# NSE2022_Electro_ESPtest_ver_1.net
KiCad netlist of a schematic drawn in EAGLE
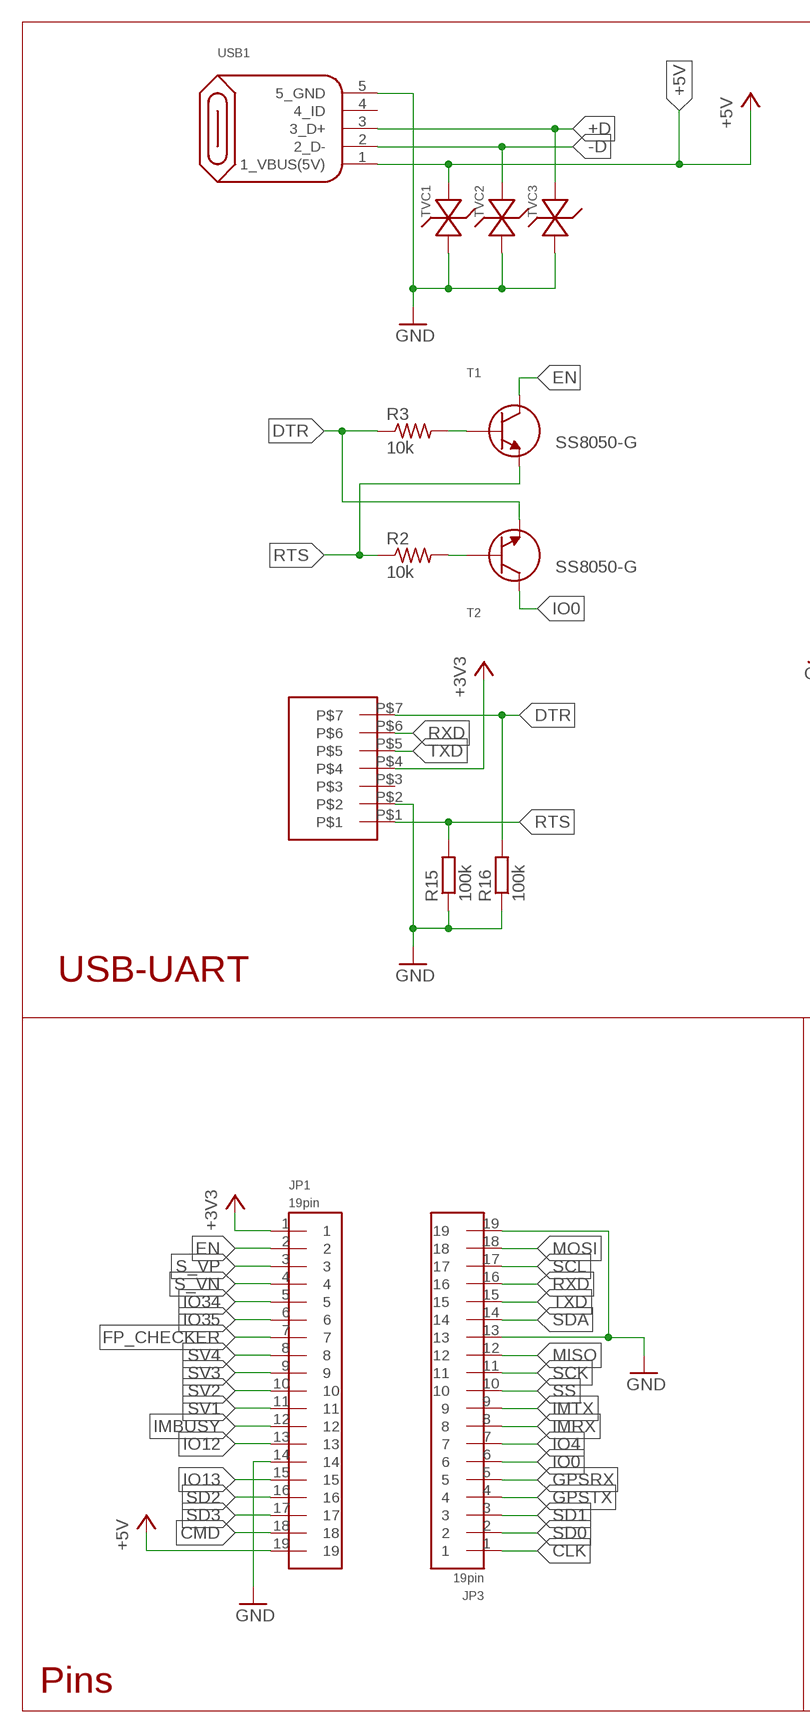
[diagram p0: schematic, sheet 1, part 1 of 2]
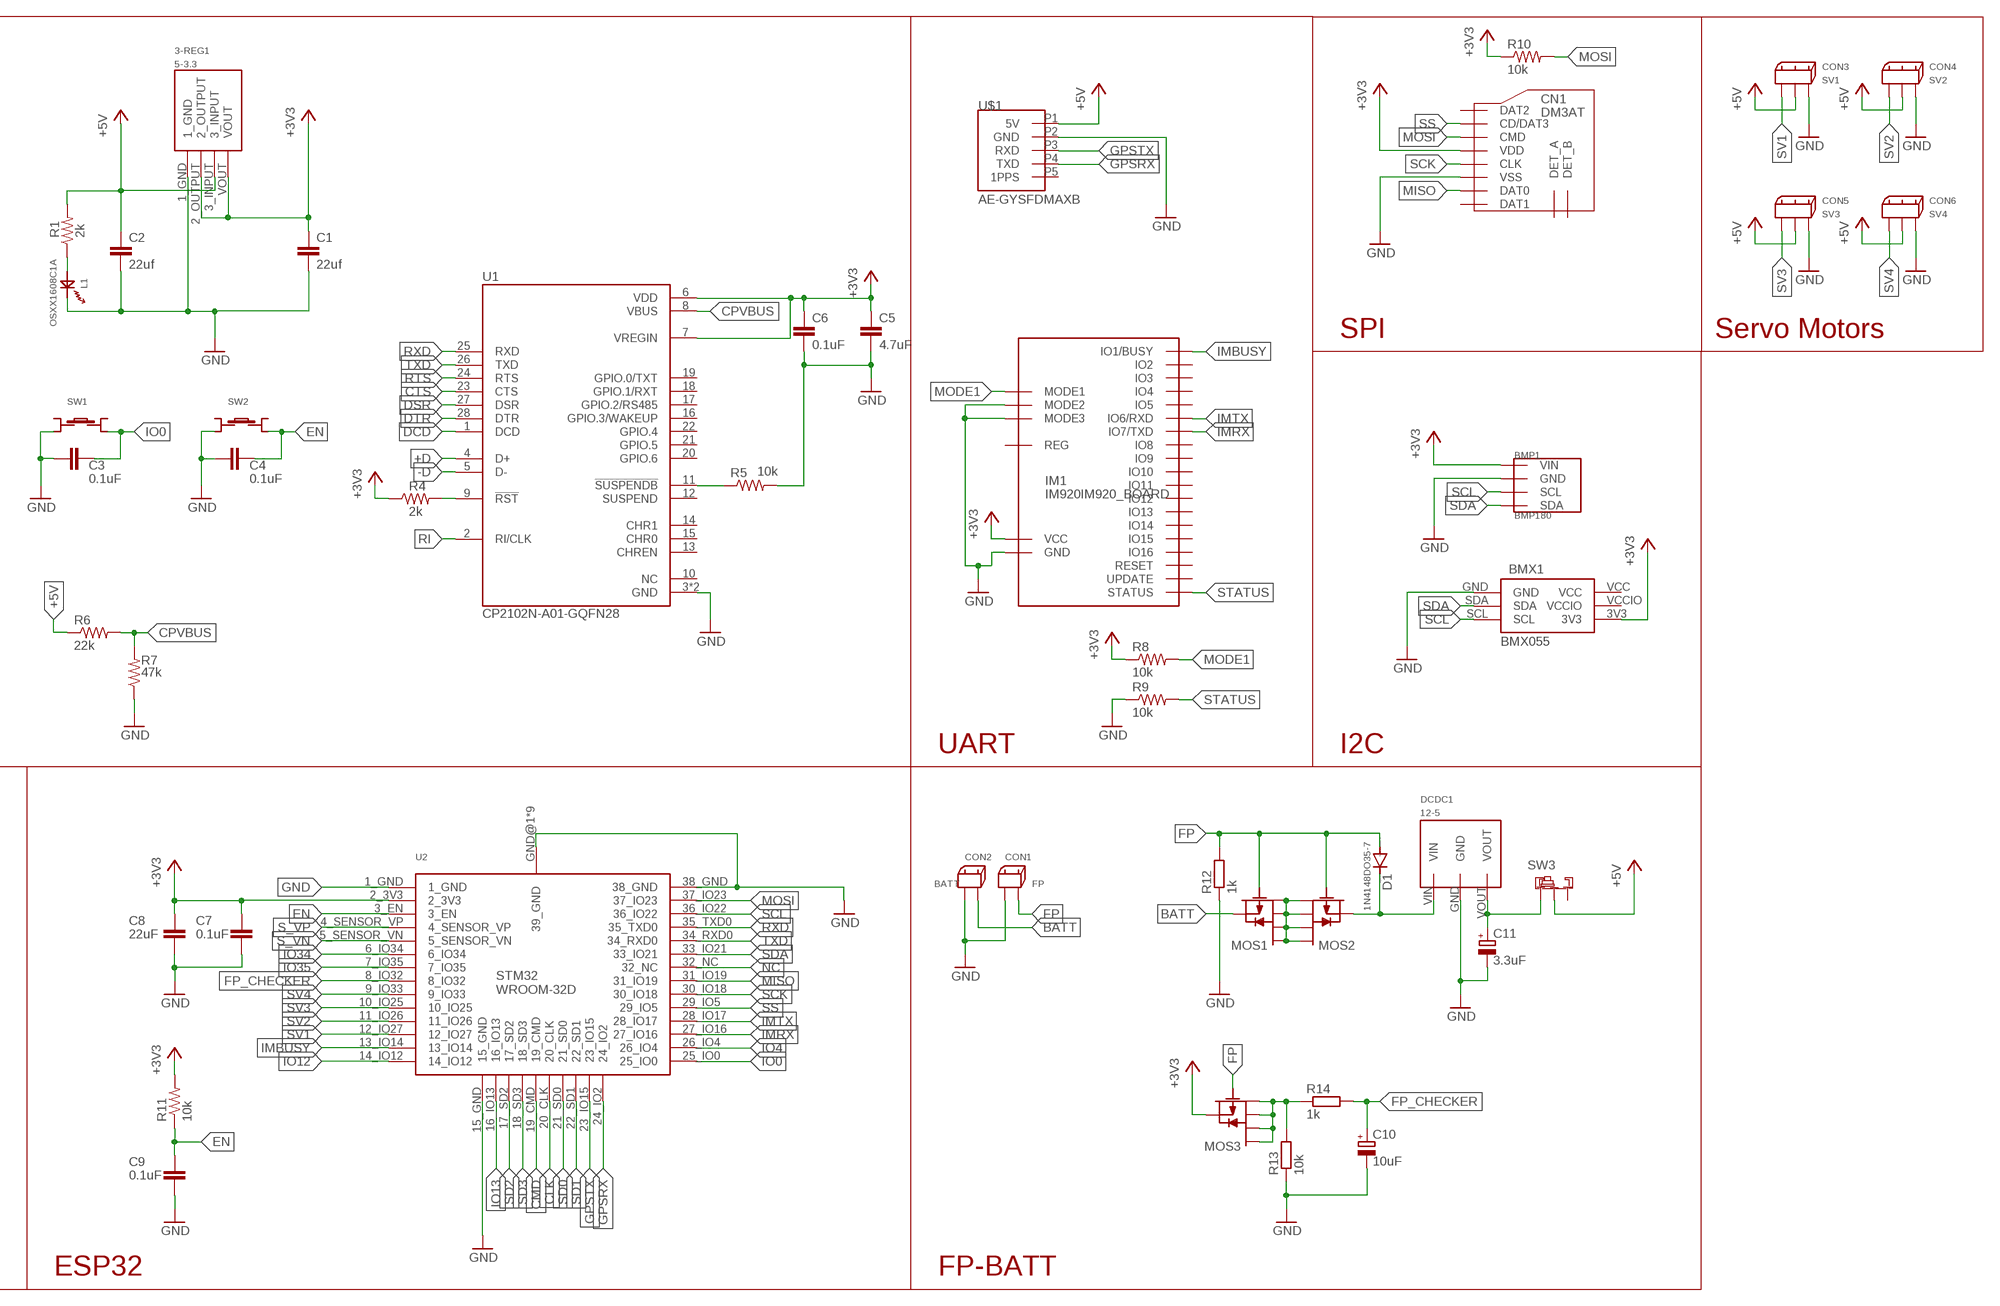
[diagram p1: schematic, sheet 1, part 2 of 2]

(export (version "E")
  (design (tool "Eeschema 10.0.6"))
  (components
    (comp (ref "3-REG1")
      (value "5-3.3")
      (footprint "eagle-import:AZ1117CH-3.3TRG1")
      (libsource (lib "eagle-import") (part "AZ1117CH-3.3TRG1"))
    )
    (comp (ref "BMP1")
      (value "BMP180")
      (footprint "eagle-import:GY-68")
      (libsource (lib "eagle-import") (part "BMP180"))
    )
    (comp (ref "BMX1")
      (value "BMX055")
      (footprint "eagle-import:BMX055")
      (libsource (lib "eagle-import") (part "BMX055"))
    )
    (comp (ref "C1")
      (value "22uf")
      (footprint "eagle-import:C0603")
      (libsource (lib "eagle-import") (part "C-EUC0603"))
    )
    (comp (ref "C2")
      (value "22uf")
      (footprint "eagle-import:C0603")
      (libsource (lib "eagle-import") (part "C-EUC0603"))
    )
    (comp (ref "C3")
      (value "0.1uF")
      (footprint "eagle-import:C0603")
      (libsource (lib "eagle-import") (part "C-EUC0603"))
    )
    (comp (ref "C4")
      (value "0.1uF")
      (footprint "eagle-import:C0603")
      (libsource (lib "eagle-import") (part "C-EUC0603"))
    )
    (comp (ref "C5")
      (value "4.7uF")
      (footprint "eagle-import:C0402")
      (libsource (lib "eagle-import") (part "C-EUC0402"))
    )
    (comp (ref "C6")
      (value "0.1uF")
      (footprint "eagle-import:C0603")
      (libsource (lib "eagle-import") (part "C-EUC0603"))
    )
    (comp (ref "C7")
      (value "0.1uF")
      (footprint "eagle-import:C0603")
      (libsource (lib "eagle-import") (part "C-EUC0603"))
    )
    (comp (ref "C8")
      (value "22uF")
      (footprint "eagle-import:C0603")
      (libsource (lib "eagle-import") (part "C-EUC0603"))
    )
    (comp (ref "C9")
      (value "0.1uF")
      (footprint "eagle-import:C0603")
      (libsource (lib "eagle-import") (part "C-EUC0603"))
    )
    (comp (ref "C10")
      (value "10uF")
      (footprint "eagle-import:E2,5-5")
      (libsource (lib "eagle-import") (part "CPOL-EUE2.5-5"))
    )
    (comp (ref "C11")
      (value "3.3uF")
      (footprint "eagle-import:E2,5-5")
      (libsource (lib "eagle-import") (part "CPOL-EUE2.5-5"))
    )
    (comp (ref "CN1")
      (value "DM3AT")
      (footprint "eagle-import:DM3AT")
      (libsource (lib "eagle-import") (part "DM3AT"))
    )
    (comp (ref "CON1")
      (value "FP")
      (footprint "eagle-import:2.5_MINI-SPOX_2PIN")
      (libsource (lib "eagle-import") (part "2.5_MINI-SPOX_2PIN"))
    )
    (comp (ref "CON2")
      (value "BATT")
      (footprint "eagle-import:2.5_MINI-SPOX_2PIN")
      (libsource (lib "eagle-import") (part "2.5_MINI-SPOX_2PIN"))
    )
    (comp (ref "CON3")
      (value "SV1")
      (footprint "eagle-import:2.5_MINI-SPOX_3PIN")
      (libsource (lib "eagle-import") (part "2.5_MINI-SPOX_3PIN"))
    )
    (comp (ref "CON4")
      (value "SV2")
      (footprint "eagle-import:2.5_MINI-SPOX_3PIN")
      (libsource (lib "eagle-import") (part "2.5_MINI-SPOX_3PIN"))
    )
    (comp (ref "CON5")
      (value "SV3")
      (footprint "eagle-import:2.5_MINI-SPOX_3PIN")
      (libsource (lib "eagle-import") (part "2.5_MINI-SPOX_3PIN"))
    )
    (comp (ref "CON6")
      (value "SV4")
      (footprint "eagle-import:2.5_MINI-SPOX_3PIN")
      (libsource (lib "eagle-import") (part "2.5_MINI-SPOX_3PIN"))
    )
    (comp (ref "D1")
      (value "1N4148DO35-7")
      (footprint "eagle-import:DO35-7")
      (libsource (lib "eagle-import") (part "1N4148DO35-7"))
    )
    (comp (ref "DCDC1")
      (value "12-5")
      (footprint "eagle-import:5V1A_M78AR05-1")
      (libsource (lib "eagle-import") (part "5V1A_M78AR05-1"))
    )
    (comp (ref "IM1")
      (value "IM920IM920_BOARD")
      (footprint "eagle-import:IM920_BOARD")
      (libsource (lib "eagle-import") (part "IM920IM920_BOARD"))
    )
    (comp (ref "JP1")
      (value "19pin")
      (footprint "eagle-import:19_2.54")
      (libsource (lib "eagle-import") (part "19_2.54"))
    )
    (comp (ref "JP2")
      (value "7pin")
      (footprint "eagle-import:7_2.54")
      (libsource (lib "eagle-import") (part "7_2.54"))
    )
    (comp (ref "JP3")
      (value "19pin")
      (footprint "eagle-import:19_2.54")
      (libsource (lib "eagle-import") (part "19_2.54"))
    )
    (comp (ref "L1")
      (value "OSXX1608C1A")
      (footprint "eagle-import:OSXX1608C1A")
      (libsource (lib "eagle-import") (part "OSXX1608C1A"))
    )
    (comp (ref "MOS1")
      (value "PCH_SSM6J808R")
      (footprint "eagle-import:SSM6J808R")
      (libsource (lib "eagle-import") (part "PCH_SSM6J808R"))
    )
    (comp (ref "MOS2")
      (value "PCH_SSM6J808R")
      (footprint "eagle-import:SSM6J808R")
      (libsource (lib "eagle-import") (part "PCH_SSM6J808R"))
    )
    (comp (ref "MOS3")
      (value "PCH_SSM6J808R")
      (footprint "eagle-import:SSM6J808R")
      (libsource (lib "eagle-import") (part "PCH_SSM6J808R"))
    )
    (comp (ref "R1")
      (value "2k")
      (footprint "eagle-import:R0201")
      (libsource (lib "eagle-import") (part "R-US_R0201"))
    )
    (comp (ref "R2")
      (value "10k")
      (footprint "eagle-import:R0201")
      (libsource (lib "eagle-import") (part "R-US_R0201"))
    )
    (comp (ref "R3")
      (value "10k")
      (footprint "eagle-import:R0201")
      (libsource (lib "eagle-import") (part "R-US_R0201"))
    )
    (comp (ref "R4")
      (value "2k")
      (footprint "eagle-import:R0201")
      (libsource (lib "eagle-import") (part "R-US_R0201"))
    )
    (comp (ref "R5")
      (value "10k")
      (footprint "eagle-import:R0201")
      (libsource (lib "eagle-import") (part "R-US_R0201"))
    )
    (comp (ref "R6")
      (value "22k")
      (footprint "eagle-import:R0201")
      (libsource (lib "eagle-import") (part "R-US_R0201"))
    )
    (comp (ref "R7")
      (value "47k")
      (footprint "eagle-import:R0201")
      (libsource (lib "eagle-import") (part "R-US_R0201"))
    )
    (comp (ref "R8")
      (value "10k")
      (footprint "eagle-import:R0201")
      (libsource (lib "eagle-import") (part "R-US_R0201"))
    )
    (comp (ref "R9")
      (value "10k")
      (footprint "eagle-import:R0201")
      (libsource (lib "eagle-import") (part "R-US_R0201"))
    )
    (comp (ref "R10")
      (value "10k")
      (footprint "eagle-import:R0201")
      (libsource (lib "eagle-import") (part "R-US_R0201"))
    )
    (comp (ref "R11")
      (value "10k")
      (footprint "eagle-import:R0201")
      (libsource (lib "eagle-import") (part "R-US_R0201"))
    )
    (comp (ref "R12")
      (value "1k")
      (footprint "eagle-import:0207_10")
      (libsource (lib "eagle-import") (part "R-EU_0207/10"))
    )
    (comp (ref "R13")
      (value "10k")
      (footprint "eagle-import:0207_10")
      (libsource (lib "eagle-import") (part "R-EU_0207/10"))
    )
    (comp (ref "R14")
      (value "1k")
      (footprint "eagle-import:0207_10")
      (libsource (lib "eagle-import") (part "R-EU_0207/10"))
    )
    (comp (ref "R15")
      (value "100k")
      (footprint "eagle-import:0207_10")
      (libsource (lib "eagle-import") (part "R-EU_0207/10"))
    )
    (comp (ref "R16")
      (value "100k")
      (footprint "eagle-import:0207_10")
      (libsource (lib "eagle-import") (part "R-EU_0207/10"))
    )
    (comp (ref "SW1")
      (value "TS-06104")
      (footprint "eagle-import:TS-06104")
      (libsource (lib "eagle-import") (part "TS-06104"))
    )
    (comp (ref "SW2")
      (value "TS-06104")
      (footprint "eagle-import:TS-06104")
      (libsource (lib "eagle-import") (part "TS-06104"))
    )
    (comp (ref "SW3")
      (value "SRIDE_SWITCH")
      (footprint "eagle-import:SRIDE_SWITCH")
      (libsource (lib "eagle-import") (part "SRIDE_SWITCH"))
    )
    (comp (ref "T1")
      (value "NPN_SS8050-G")
      (footprint "eagle-import:NPN_SS8050-G")
      (libsource (lib "eagle-import") (part "NPN_SS8050-G"))
    )
    (comp (ref "T2")
      (value "NPN_SS8050-G")
      (footprint "eagle-import:NPN_SS8050-G")
      (libsource (lib "eagle-import") (part "NPN_SS8050-G"))
    )
    (comp (ref "TVC1")
      (value "ESD5484FCT5G")
      (footprint "eagle-import:ESD5484FCT5G")
      (libsource (lib "eagle-import") (part "ESD5484FCT5G"))
    )
    (comp (ref "TVC2")
      (value "ESD5484FCT5G")
      (footprint "eagle-import:ESD5484FCT5G")
      (libsource (lib "eagle-import") (part "ESD5484FCT5G"))
    )
    (comp (ref "TVC3")
      (value "ESD5484FCT5G")
      (footprint "eagle-import:ESD5484FCT5G")
      (libsource (lib "eagle-import") (part "ESD5484FCT5G"))
    )
    (comp (ref "U$1")
      (value "AE-GYSFDMAXB")
      (footprint "eagle-import:AE-GYSFDMAXB")
      (libsource (lib "eagle-import") (part "AE-GYSFDMAXB"))
    )
    (comp (ref "U1")
      (value "CP2102N-A01-GQFN28")
      (footprint "eagle-import:QFN50P500X500X80-29N")
      (fields (field (name "MF") "Silicon Labs"))
      (libsource (lib "eagle-import") (part "CP2102N-A01-GQFN28"))
    )
    (comp (ref "U2")
      (value "ESP32-WROOM-32D")
      (footprint "eagle-import:ESP32-WROOM-32D")
      (libsource (lib "eagle-import") (part "ESP32-WROOM-32D"))
    )
    (comp (ref "USB1")
      (value "MICRO-B_ZX62R-B-5P")
      (footprint "eagle-import:MICRO-B_ZX62R-B-5P")
      (libsource (lib "eagle-import") (part "MICRO-B_ZX62R-B-5P"))
    )
  )
  (nets
    (net (code "1") (name "+3V3") (class "Default")
      (node (ref "3-REG1") (pin "2_OUTPUT") (pinfunction "2_OUTPUT_2_OUTPUT") (pintype "bidirectional"))
      (node (ref "3-REG1") (pin "VOUT") (pinfunction "VOUT_VOUT") (pintype "bidirectional"))
      (node (ref "BMP1") (pin "P1") (pinfunction "VIN_P1") (pintype "bidirectional"))
      (node (ref "BMX1") (pin "3V3") (pinfunction "3V3_3V3") (pintype "power_in"))
      (node (ref "C1") (pin "1") (pinfunction "1_1") (pintype "passive"))
      (node (ref "C5") (pin "1") (pinfunction "1_1") (pintype "passive"))
      (node (ref "C6") (pin "1") (pinfunction "1_1") (pintype "passive"))
      (node (ref "C7") (pin "1") (pinfunction "1_1") (pintype "passive"))
      (node (ref "C8") (pin "1") (pinfunction "1_1") (pintype "passive"))
      (node (ref "CN1") (pin "VDD") (pinfunction "VDD_VDD") (pintype "bidirectional"))
      (node (ref "IM1") (pin "IO23") (pinfunction "VCC_IO23") (pintype "bidirectional"))
      (node (ref "JP1") (pin "1") (pinfunction "1_1") (pintype "bidirectional"))
      (node (ref "JP2") (pin "P$4") (pinfunction "P$4_P$4") (pintype "bidirectional"))
      (node (ref "MOS3") (pin "S") (pinfunction "S_S") (pintype "bidirectional"))
      (node (ref "R10") (pin "1") (pinfunction "1_1") (pintype "passive"))
      (node (ref "R11") (pin "2") (pinfunction "2_2") (pintype "passive"))
      (node (ref "R4") (pin "1") (pinfunction "1_1") (pintype "passive"))
      (node (ref "R8") (pin "1") (pinfunction "1_1") (pintype "passive"))
      (node (ref "U1") (pin "6") (pinfunction "VDD_6") (pintype "power_in"))
      (node (ref "U1") (pin "7") (pinfunction "VREGIN_7") (pintype "power_in"))
      (node (ref "U2") (pin "2_3V3") (pinfunction "2_3V3_2_3V3") (pintype "bidirectional"))
    )
    (net (code "2") (name "+5V") (class "Default")
      (node (ref "3-REG1") (pin "3_INPUT") (pinfunction "3_INPUT_3_INPUT") (pintype "bidirectional"))
      (node (ref "C2") (pin "1") (pinfunction "1_1") (pintype "passive"))
      (node (ref "CON3") (pin "2") (pinfunction "2_2") (pintype "bidirectional"))
      (node (ref "CON4") (pin "2") (pinfunction "2_2") (pintype "bidirectional"))
      (node (ref "CON5") (pin "2") (pinfunction "2_2") (pintype "bidirectional"))
      (node (ref "CON6") (pin "2") (pinfunction "2_2") (pintype "bidirectional"))
      (node (ref "JP1") (pin "19") (pinfunction "19_19") (pintype "bidirectional"))
      (node (ref "R1") (pin "2") (pinfunction "2_2") (pintype "passive"))
      (node (ref "R6") (pin "1") (pinfunction "1_1") (pintype "passive"))
      (node (ref "SW3") (pin "LR") (pinfunction "LR_LR") (pintype "bidirectional"))
      (node (ref "TVC1") (pin "2_AN") (pinfunction "2_AN_2_AN") (pintype "bidirectional"))
      (node (ref "U$1") (pin "P1") (pinfunction "5V_P1") (pintype "bidirectional"))
      (node (ref "USB1") (pin "1") (pinfunction "1_VBUS(5V)_1") (pintype "bidirectional"))
    )
    (net (code "3") (name "+D") (class "Default")
      (node (ref "TVC3") (pin "2_AN") (pinfunction "2_AN_2_AN") (pintype "bidirectional"))
      (node (ref "U1") (pin "4") (pinfunction "D+_4") (pintype "bidirectional"))
      (node (ref "USB1") (pin "3") (pinfunction "3_D+_3") (pintype "bidirectional"))
    )
    (net (code "4") (name "-D") (class "Default")
      (node (ref "TVC2") (pin "2_AN") (pinfunction "2_AN_2_AN") (pintype "bidirectional"))
      (node (ref "U1") (pin "5") (pinfunction "D-_5") (pintype "bidirectional"))
      (node (ref "USB1") (pin "2") (pinfunction "2_D-_2") (pintype "bidirectional"))
    )
    (net (code "5") (name "/VCC") (class "Default")
      (node (ref "BMX1") (pin "VCC") (pinfunction "VCC_VCC") (pintype "power_in"))
    )
    (net (code "6") (name "/VCCIO") (class "Default")
      (node (ref "BMX1") (pin "VCCIO") (pinfunction "VCCIO_VCCIO") (pintype "power_in"))
    )
    (net (code "7") (name "BATT") (class "Default")
      (node (ref "CON2") (pin "2") (pinfunction "2_2") (pintype "bidirectional"))
      (node (ref "MOS1") (pin "S") (pinfunction "S_S") (pintype "bidirectional"))
    )
    (net (code "8") (name "CLK") (class "Default")
      (node (ref "JP3") (pin "1") (pinfunction "1_1") (pintype "bidirectional"))
      (node (ref "U2") (pin "20_CLK") (pinfunction "20_CLK_20_CLK") (pintype "bidirectional"))
    )
    (net (code "9") (name "CMD") (class "Default")
      (node (ref "JP1") (pin "18") (pinfunction "18_18") (pintype "bidirectional"))
      (node (ref "U2") (pin "19_CMD") (pinfunction "19_CMD_19_CMD") (pintype "bidirectional"))
    )
    (net (code "10") (name "CPVBUS") (class "Default")
      (node (ref "R6") (pin "2") (pinfunction "2_2") (pintype "passive"))
      (node (ref "R7") (pin "2") (pinfunction "2_2") (pintype "passive"))
      (node (ref "U1") (pin "8") (pinfunction "VBUS_8") (pintype "power_in"))
    )
    (net (code "11") (name "CTS") (class "Default")
      (node (ref "U1") (pin "23") (pinfunction "CTS_23") (pintype "input"))
    )
    (net (code "12") (name "DCD") (class "Default")
      (node (ref "U1") (pin "1") (pinfunction "DCD_1") (pintype "input"))
    )
    (net (code "13") (name "DSR") (class "Default")
      (node (ref "U1") (pin "27") (pinfunction "DSR_27") (pintype "input"))
    )
    (net (code "14") (name "DTR") (class "Default")
      (node (ref "JP2") (pin "P$7") (pinfunction "P$7_P$7") (pintype "bidirectional"))
      (node (ref "R16") (pin "2") (pinfunction "2_2") (pintype "passive"))
      (node (ref "R3") (pin "1") (pinfunction "1_1") (pintype "passive"))
      (node (ref "T2") (pin "2") (pinfunction "2_2") (pintype "bidirectional"))
      (node (ref "U1") (pin "28") (pinfunction "DTR_28") (pintype "output"))
    )
    (net (code "15") (name "EN") (class "Default")
      (node (ref "C4") (pin "1") (pinfunction "1_1") (pintype "passive"))
      (node (ref "C9") (pin "1") (pinfunction "1_1") (pintype "passive"))
      (node (ref "JP1") (pin "2") (pinfunction "2_2") (pintype "bidirectional"))
      (node (ref "R11") (pin "1") (pinfunction "1_1") (pintype "passive"))
      (node (ref "SW2") (pin "D") (pinfunction "D_D") (pintype "bidirectional"))
      (node (ref "T1") (pin "3") (pinfunction "3_3") (pintype "bidirectional"))
      (node (ref "U2") (pin "3_EN") (pinfunction "3_EN_3_EN") (pintype "bidirectional"))
    )
    (net (code "16") (name "FP") (class "Default")
      (node (ref "CON1") (pin "2") (pinfunction "2_2") (pintype "bidirectional"))
      (node (ref "D1") (pin "A") (pinfunction "A_A") (pintype "passive"))
      (node (ref "MOS1") (pin "G") (pinfunction "G_G") (pintype "bidirectional"))
      (node (ref "MOS2") (pin "G") (pinfunction "G_G") (pintype "bidirectional"))
      (node (ref "MOS3") (pin "G") (pinfunction "G_G") (pintype "bidirectional"))
      (node (ref "R12") (pin "2") (pinfunction "2_2") (pintype "passive"))
    )
    (net (code "17") (name "FP_CHECKER") (class "Default")
      (node (ref "C10") (pin "+") (pinfunction "+_+") (pintype "passive"))
      (node (ref "JP1") (pin "7") (pinfunction "7_7") (pintype "bidirectional"))
      (node (ref "R14") (pin "2") (pinfunction "2_2") (pintype "passive"))
      (node (ref "U2") (pin "8_IO32") (pinfunction "8_IO32_8_IO32") (pintype "bidirectional"))
    )
    (net (code "18") (name "GND") (class "Default")
      (node (ref "3-REG1") (pin "1_GND") (pinfunction "1_GND_1_GND") (pintype "bidirectional"))
      (node (ref "BMP1") (pin "P2") (pinfunction "GND_P2") (pintype "bidirectional"))
      (node (ref "BMX1") (pin "GND") (pinfunction "GND_GND") (pintype "power_in"))
      (node (ref "C1") (pin "2") (pinfunction "2_2") (pintype "passive"))
      (node (ref "C10") (pin "-") (pinfunction "-_-") (pintype "passive"))
      (node (ref "C11") (pin "-") (pinfunction "-_-") (pintype "passive"))
      (node (ref "C2") (pin "2") (pinfunction "2_2") (pintype "passive"))
      (node (ref "C3") (pin "2") (pinfunction "2_2") (pintype "passive"))
      (node (ref "C4") (pin "2") (pinfunction "2_2") (pintype "passive"))
      (node (ref "C5") (pin "2") (pinfunction "2_2") (pintype "passive"))
      (node (ref "C6") (pin "2") (pinfunction "2_2") (pintype "passive"))
      (node (ref "C7") (pin "2") (pinfunction "2_2") (pintype "passive"))
      (node (ref "C8") (pin "2") (pinfunction "2_2") (pintype "passive"))
      (node (ref "C9") (pin "2") (pinfunction "2_2") (pintype "passive"))
      (node (ref "CN1") (pin "VSS") (pinfunction "VSS_VSS") (pintype "bidirectional"))
      (node (ref "CON1") (pin "1") (pinfunction "1_1") (pintype "bidirectional"))
      (node (ref "CON2") (pin "1") (pinfunction "1_1") (pintype "bidirectional"))
      (node (ref "CON3") (pin "3") (pinfunction "3_3") (pintype "bidirectional"))
      (node (ref "CON4") (pin "3") (pinfunction "3_3") (pintype "bidirectional"))
      (node (ref "CON5") (pin "3") (pinfunction "3_3") (pintype "bidirectional"))
      (node (ref "CON6") (pin "3") (pinfunction "3_3") (pintype "bidirectional"))
      (node (ref "DCDC1") (pin "GND") (pinfunction "GND_GND") (pintype "bidirectional"))
      (node (ref "IM1") (pin "IO18") (pinfunction "MODE2_IO18") (pintype "bidirectional"))
      (node (ref "IM1") (pin "IO19") (pinfunction "MODE3_IO19") (pintype "bidirectional"))
      (node (ref "IM1") (pin "IO24") (pinfunction "GND_IO24") (pintype "bidirectional"))
      (node (ref "JP1") (pin "14") (pinfunction "14_14") (pintype "bidirectional"))
      (node (ref "JP2") (pin "P$2") (pinfunction "P$2_P$2") (pintype "bidirectional"))
      (node (ref "JP3") (pin "13") (pinfunction "13_13") (pintype "bidirectional"))
      (node (ref "JP3") (pin "19") (pinfunction "19_19") (pintype "bidirectional"))
      (node (ref "L1") (pin "CT") (pinfunction "CT_CT") (pintype "bidirectional"))
      (node (ref "R12") (pin "1") (pinfunction "1_1") (pintype "passive"))
      (node (ref "R13") (pin "1") (pinfunction "1_1") (pintype "passive"))
      (node (ref "R15") (pin "1") (pinfunction "1_1") (pintype "passive"))
      (node (ref "R16") (pin "1") (pinfunction "1_1") (pintype "passive"))
      (node (ref "R5") (pin "2") (pinfunction "2_2") (pintype "passive"))
      (node (ref "R7") (pin "1") (pinfunction "1_1") (pintype "passive"))
      (node (ref "R9") (pin "1") (pinfunction "1_1") (pintype "passive"))
      (node (ref "SW1") (pin "B") (pinfunction "B_B") (pintype "bidirectional"))
      (node (ref "SW2") (pin "B") (pinfunction "B_B") (pintype "bidirectional"))
      (node (ref "TVC1") (pin "1_CT") (pinfunction "1_CT_1_CT") (pintype "bidirectional"))
      (node (ref "TVC2") (pin "1_CT") (pinfunction "1_CT_1_CT") (pintype "bidirectional"))
      (node (ref "TVC3") (pin "1_CT") (pinfunction "1_CT_1_CT") (pintype "bidirectional"))
      (node (ref "U$1") (pin "P2") (pinfunction "GND_P2") (pintype "bidirectional"))
      (node (ref "U1") (pin "29") (pinfunction "GND_29") (pintype "power_in"))
      (node (ref "U1") (pin "3") (pinfunction "GND_3") (pintype "power_in"))
      (node (ref "U2") (pin "15_GND") (pinfunction "15_GND_15_GND") (pintype "bidirectional"))
      (node (ref "U2") (pin "1_GND") (pinfunction "1_GND_1_GND") (pintype "bidirectional"))
      (node (ref "U2") (pin "38_GND") (pinfunction "38_GND_38_GND") (pintype "bidirectional"))
      (node (ref "U2") (pin "GND@1") (pinfunction "39_GND_GND@1") (pintype "bidirectional"))
      (node (ref "U2") (pin "GND@2") (pinfunction "39_GND_GND@2") (pintype "bidirectional"))
      (node (ref "U2") (pin "GND@3") (pinfunction "39_GND_GND@3") (pintype "bidirectional"))
      (node (ref "U2") (pin "GND@4") (pinfunction "39_GND_GND@4") (pintype "bidirectional"))
      (node (ref "U2") (pin "GND@5") (pinfunction "39_GND_GND@5") (pintype "bidirectional"))
      (node (ref "U2") (pin "GND@6") (pinfunction "39_GND_GND@6") (pintype "bidirectional"))
      (node (ref "U2") (pin "GND@7") (pinfunction "39_GND_GND@7") (pintype "bidirectional"))
      (node (ref "U2") (pin "GND@8") (pinfunction "39_GND_GND@8") (pintype "bidirectional"))
      (node (ref "U2") (pin "GND@9") (pinfunction "39_GND_GND@9") (pintype "bidirectional"))
      (node (ref "USB1") (pin "5") (pinfunction "5_GND_5") (pintype "bidirectional"))
    )
    (net (code "19") (name "GPSRX") (class "Default")
      (node (ref "JP3") (pin "5") (pinfunction "5_5") (pintype "bidirectional"))
      (node (ref "U$1") (pin "P4") (pinfunction "TXD_P4") (pintype "bidirectional"))
      (node (ref "U2") (pin "24_IO2") (pinfunction "24_IO2_24_IO2") (pintype "bidirectional"))
    )
    (net (code "20") (name "GPSTX") (class "Default")
      (node (ref "JP3") (pin "4") (pinfunction "4_4") (pintype "bidirectional"))
      (node (ref "U$1") (pin "P3") (pinfunction "RXD_P3") (pintype "bidirectional"))
      (node (ref "U2") (pin "23_IO15") (pinfunction "23_IO15_23_IO15") (pintype "bidirectional"))
    )
    (net (code "21") (name "IMBUSY") (class "Default")
      (node (ref "IM1") (pin "IO1") (pinfunction "IO1/BUSY_IO1") (pintype "bidirectional"))
      (node (ref "JP1") (pin "12") (pinfunction "12_12") (pintype "bidirectional"))
      (node (ref "U2") (pin "13_IO14") (pinfunction "13_IO14_13_IO14") (pintype "bidirectional"))
    )
    (net (code "22") (name "IMRX") (class "Default")
      (node (ref "IM1") (pin "IO7") (pinfunction "IO7/TXD_IO7") (pintype "bidirectional"))
      (node (ref "JP3") (pin "8") (pinfunction "8_8") (pintype "bidirectional"))
      (node (ref "U2") (pin "27_IO16") (pinfunction "27_IO16_27_IO16") (pintype "bidirectional"))
    )
    (net (code "23") (name "IMTX") (class "Default")
      (node (ref "IM1") (pin "IO6") (pinfunction "IO6/RXD_IO6") (pintype "bidirectional"))
      (node (ref "JP3") (pin "9") (pinfunction "9_9") (pintype "bidirectional"))
      (node (ref "U2") (pin "28_IO17") (pinfunction "28_IO17_28_IO17") (pintype "bidirectional"))
    )
    (net (code "24") (name "IO0") (class "Default")
      (node (ref "C3") (pin "1") (pinfunction "1_1") (pintype "passive"))
      (node (ref "JP3") (pin "6") (pinfunction "6_6") (pintype "bidirectional"))
      (node (ref "SW1") (pin "D") (pinfunction "D_D") (pintype "bidirectional"))
      (node (ref "T2") (pin "3") (pinfunction "3_3") (pintype "bidirectional"))
      (node (ref "U2") (pin "25_IO0") (pinfunction "25_IO0_25_IO0") (pintype "bidirectional"))
    )
    (net (code "25") (name "IO4") (class "Default")
      (node (ref "JP3") (pin "7") (pinfunction "7_7") (pintype "bidirectional"))
      (node (ref "U2") (pin "26_IO4") (pinfunction "26_IO4_26_IO4") (pintype "bidirectional"))
    )
    (net (code "26") (name "IO12") (class "Default")
      (node (ref "JP1") (pin "13") (pinfunction "13_13") (pintype "bidirectional"))
      (node (ref "U2") (pin "14_IO12") (pinfunction "14_IO12_14_IO12") (pintype "bidirectional"))
    )
    (net (code "27") (name "IO13") (class "Default")
      (node (ref "JP1") (pin "15") (pinfunction "15_15") (pintype "bidirectional"))
      (node (ref "U2") (pin "16_IO13") (pinfunction "16_IO13_16_IO13") (pintype "bidirectional"))
    )
    (net (code "28") (name "IO34") (class "Default")
      (node (ref "JP1") (pin "5") (pinfunction "5_5") (pintype "bidirectional"))
      (node (ref "U2") (pin "6_IO34") (pinfunction "6_IO34_6_IO34") (pintype "bidirectional"))
    )
    (net (code "29") (name "IO35") (class "Default")
      (node (ref "JP1") (pin "6") (pinfunction "6_6") (pintype "bidirectional"))
      (node (ref "U2") (pin "7_IO35") (pinfunction "7_IO35_7_IO35") (pintype "bidirectional"))
    )
    (net (code "30") (name "MISO") (class "Default")
      (node (ref "CN1") (pin "DAT0") (pinfunction "DAT0_DAT0") (pintype "bidirectional"))
      (node (ref "JP3") (pin "12") (pinfunction "12_12") (pintype "bidirectional"))
      (node (ref "U2") (pin "31_IO19") (pinfunction "31_IO19_31_IO19") (pintype "bidirectional"))
    )
    (net (code "31") (name "MODE1") (class "Default")
      (node (ref "IM1") (pin "IO17") (pinfunction "MODE1_IO17") (pintype "bidirectional"))
      (node (ref "R8") (pin "2") (pinfunction "2_2") (pintype "passive"))
    )
    (net (code "32") (name "MOSI") (class "Default")
      (node (ref "CN1") (pin "CMD") (pinfunction "CMD_CMD") (pintype "bidirectional"))
      (node (ref "JP3") (pin "18") (pinfunction "18_18") (pintype "bidirectional"))
      (node (ref "R10") (pin "2") (pinfunction "2_2") (pintype "passive"))
      (node (ref "U2") (pin "37_IO23") (pinfunction "37_IO23_37_IO23") (pintype "bidirectional"))
    )
    (net (code "33") (name "NC") (class "Default")
      (node (ref "U2") (pin "32_NC") (pinfunction "32_NC_32_NC") (pintype "bidirectional"))
    )
    (net (code "34") (name "Net-(C11-Pad+)") (class "Default")
      (node (ref "C11") (pin "+") (pinfunction "+_+") (pintype "passive"))
      (node (ref "DCDC1") (pin "VOUT") (pinfunction "VOUT_VOUT") (pintype "bidirectional"))
      (node (ref "SW3") (pin "L") (pinfunction "L_L") (pintype "bidirectional"))
    )
    (net (code "35") (name "Net-(D1-PadC)") (class "Default")
      (node (ref "D1") (pin "C") (pinfunction "C_C") (pintype "passive"))
      (node (ref "DCDC1") (pin "VIN") (pinfunction "VIN_VIN") (pintype "bidirectional"))
      (node (ref "MOS2") (pin "S") (pinfunction "S_S") (pintype "bidirectional"))
    )
    (net (code "36") (name "Net-(L1-PadAN)") (class "Default")
      (node (ref "L1") (pin "AN") (pinfunction "AN_AN") (pintype "bidirectional"))
      (node (ref "R1") (pin "1") (pinfunction "1_1") (pintype "passive"))
    )
    (net (code "37") (name "Net-(MOS1-PadD1)") (class "Default")
      (node (ref "MOS1") (pin "D1") (pinfunction "D1_D1") (pintype "bidirectional"))
      (node (ref "MOS1") (pin "D2") (pinfunction "D2_D2") (pintype "bidirectional"))
      (node (ref "MOS1") (pin "D3") (pinfunction "D3_D3") (pintype "bidirectional"))
      (node (ref "MOS1") (pin "D4") (pinfunction "D4_D4") (pintype "bidirectional"))
      (node (ref "MOS2") (pin "D1") (pinfunction "D1_D1") (pintype "bidirectional"))
      (node (ref "MOS2") (pin "D2") (pinfunction "D2_D2") (pintype "bidirectional"))
      (node (ref "MOS2") (pin "D3") (pinfunction "D3_D3") (pintype "bidirectional"))
      (node (ref "MOS2") (pin "D4") (pinfunction "D4_D4") (pintype "bidirectional"))
    )
    (net (code "38") (name "Net-(MOS3-PadD1)") (class "Default")
      (node (ref "MOS3") (pin "D1") (pinfunction "D1_D1") (pintype "bidirectional"))
      (node (ref "MOS3") (pin "D2") (pinfunction "D2_D2") (pintype "bidirectional"))
      (node (ref "MOS3") (pin "D3") (pinfunction "D3_D3") (pintype "bidirectional"))
      (node (ref "MOS3") (pin "D4") (pinfunction "D4_D4") (pintype "bidirectional"))
      (node (ref "R13") (pin "2") (pinfunction "2_2") (pintype "passive"))
      (node (ref "R14") (pin "1") (pinfunction "1_1") (pintype "passive"))
    )
    (net (code "39") (name "Net-(R2-Pad2)") (class "Default")
      (node (ref "R2") (pin "2") (pinfunction "2_2") (pintype "passive"))
      (node (ref "T2") (pin "1") (pinfunction "1_1") (pintype "bidirectional"))
    )
    (net (code "40") (name "Net-(R3-Pad2)") (class "Default")
      (node (ref "R3") (pin "2") (pinfunction "2_2") (pintype "passive"))
      (node (ref "T1") (pin "1") (pinfunction "1_1") (pintype "bidirectional"))
    )
    (net (code "41") (name "Net-(U1-~{RST})") (class "Default")
      (node (ref "R4") (pin "2") (pinfunction "2_2") (pintype "passive"))
      (node (ref "U1") (pin "9") (pinfunction "~{RST}_9") (pintype "input"))
    )
    (net (code "42") (name "Net-(U1-~{SUSPENDB})") (class "Default")
      (node (ref "R5") (pin "1") (pinfunction "1_1") (pintype "passive"))
      (node (ref "U1") (pin "11") (pinfunction "~{SUSPENDB}_11") (pintype "output"))
    )
    (net (code "43") (name "RI") (class "Default")
      (node (ref "U1") (pin "2") (pinfunction "RI/CLK_2") (pintype "bidirectional"))
    )
    (net (code "44") (name "RTS") (class "Default")
      (node (ref "JP2") (pin "P$1") (pinfunction "P$1_P$1") (pintype "bidirectional"))
      (node (ref "R15") (pin "2") (pinfunction "2_2") (pintype "passive"))
      (node (ref "R2") (pin "1") (pinfunction "1_1") (pintype "passive"))
      (node (ref "T1") (pin "2") (pinfunction "2_2") (pintype "bidirectional"))
      (node (ref "U1") (pin "24") (pinfunction "RTS_24") (pintype "output"))
    )
    (net (code "45") (name "RXD") (class "Default")
      (node (ref "JP2") (pin "P$6") (pinfunction "P$6_P$6") (pintype "bidirectional"))
      (node (ref "JP3") (pin "16") (pinfunction "16_16") (pintype "bidirectional"))
      (node (ref "U1") (pin "25") (pinfunction "RXD_25") (pintype "input"))
      (node (ref "U2") (pin "35_TXD0") (pinfunction "35_TXD0_35_TXD0") (pintype "bidirectional"))
    )
    (net (code "46") (name "SCK") (class "Default")
      (node (ref "CN1") (pin "CLK") (pinfunction "CLK_CLK") (pintype "bidirectional"))
      (node (ref "JP3") (pin "11") (pinfunction "11_11") (pintype "bidirectional"))
      (node (ref "U2") (pin "30_IO18") (pinfunction "30_IO18_30_IO18") (pintype "bidirectional"))
    )
    (net (code "47") (name "SCL") (class "Default")
      (node (ref "BMP1") (pin "P3") (pinfunction "SCL_P3") (pintype "bidirectional"))
      (node (ref "BMX1") (pin "SCL") (pinfunction "SCL_SCL") (pintype "bidirectional"))
      (node (ref "JP3") (pin "17") (pinfunction "17_17") (pintype "bidirectional"))
      (node (ref "U2") (pin "36_IO22") (pinfunction "36_IO22_36_IO22") (pintype "bidirectional"))
    )
    (net (code "48") (name "SD0") (class "Default")
      (node (ref "JP3") (pin "2") (pinfunction "2_2") (pintype "bidirectional"))
      (node (ref "U2") (pin "21_SD0") (pinfunction "21_SD0_21_SD0") (pintype "bidirectional"))
    )
    (net (code "49") (name "SD1") (class "Default")
      (node (ref "JP3") (pin "3") (pinfunction "3_3") (pintype "bidirectional"))
      (node (ref "U2") (pin "22_SD1") (pinfunction "22_SD1_22_SD1") (pintype "bidirectional"))
    )
    (net (code "50") (name "SD2") (class "Default")
      (node (ref "JP1") (pin "16") (pinfunction "16_16") (pintype "bidirectional"))
      (node (ref "U2") (pin "17_SD2") (pinfunction "17_SD2_17_SD2") (pintype "bidirectional"))
    )
    (net (code "51") (name "SD3") (class "Default")
      (node (ref "JP1") (pin "17") (pinfunction "17_17") (pintype "bidirectional"))
      (node (ref "U2") (pin "18_SD3") (pinfunction "18_SD3_18_SD3") (pintype "bidirectional"))
    )
    (net (code "52") (name "SDA") (class "Default")
      (node (ref "BMP1") (pin "P4") (pinfunction "SDA_P4") (pintype "bidirectional"))
      (node (ref "BMX1") (pin "SDA") (pinfunction "SDA_SDA") (pintype "bidirectional"))
      (node (ref "JP3") (pin "14") (pinfunction "14_14") (pintype "bidirectional"))
      (node (ref "U2") (pin "33_IO21") (pinfunction "33_IO21_33_IO21") (pintype "bidirectional"))
    )
    (net (code "53") (name "SS") (class "Default")
      (node (ref "CN1") (pin "CD/DAT3") (pinfunction "CD/DAT3_CD/DAT3") (pintype "bidirectional"))
      (node (ref "JP3") (pin "10") (pinfunction "10_10") (pintype "bidirectional"))
      (node (ref "U2") (pin "29_IO5") (pinfunction "29_IO5_29_IO5") (pintype "bidirectional"))
    )
    (net (code "54") (name "STATUS") (class "Default")
      (node (ref "IM1") (pin "IO21") (pinfunction "STATUS_IO21") (pintype "bidirectional"))
      (node (ref "R9") (pin "2") (pinfunction "2_2") (pintype "passive"))
    )
    (net (code "55") (name "SV1") (class "Default")
      (node (ref "CON3") (pin "1") (pinfunction "1_1") (pintype "bidirectional"))
      (node (ref "JP1") (pin "11") (pinfunction "11_11") (pintype "bidirectional"))
      (node (ref "U2") (pin "12_IO27") (pinfunction "12_IO27_12_IO27") (pintype "bidirectional"))
    )
    (net (code "56") (name "SV2") (class "Default")
      (node (ref "CON4") (pin "1") (pinfunction "1_1") (pintype "bidirectional"))
      (node (ref "JP1") (pin "10") (pinfunction "10_10") (pintype "bidirectional"))
      (node (ref "U2") (pin "11_IO26") (pinfunction "11_IO26_11_IO26") (pintype "bidirectional"))
    )
    (net (code "57") (name "SV3") (class "Default")
      (node (ref "CON5") (pin "1") (pinfunction "1_1") (pintype "bidirectional"))
      (node (ref "JP1") (pin "9") (pinfunction "9_9") (pintype "bidirectional"))
      (node (ref "U2") (pin "10_IO25") (pinfunction "10_IO25_10_IO25") (pintype "bidirectional"))
    )
    (net (code "58") (name "SV4") (class "Default")
      (node (ref "CON6") (pin "1") (pinfunction "1_1") (pintype "bidirectional"))
      (node (ref "JP1") (pin "8") (pinfunction "8_8") (pintype "bidirectional"))
      (node (ref "U2") (pin "9_IO33") (pinfunction "9_IO33_9_IO33") (pintype "bidirectional"))
    )
    (net (code "59") (name "S_VN") (class "Default")
      (node (ref "JP1") (pin "4") (pinfunction "4_4") (pintype "bidirectional"))
      (node (ref "U2") (pin "5_SENSOR_VN") (pinfunction "5_SENSOR_VN_5_SENSOR_VN") (pintype "bidirectional"))
    )
    (net (code "60") (name "S_VP") (class "Default")
      (node (ref "JP1") (pin "3") (pinfunction "3_3") (pintype "bidirectional"))
      (node (ref "U2") (pin "4_SENSOR_VP") (pinfunction "4_SENSOR_VP_4_SENSOR_VP") (pintype "bidirectional"))
    )
    (net (code "61") (name "TXD") (class "Default")
      (node (ref "JP2") (pin "P$5") (pinfunction "P$5_P$5") (pintype "bidirectional"))
      (node (ref "JP3") (pin "15") (pinfunction "15_15") (pintype "bidirectional"))
      (node (ref "U1") (pin "26") (pinfunction "TXD_26") (pintype "output"))
      (node (ref "U2") (pin "34_RXD0") (pinfunction "34_RXD0_34_RXD0") (pintype "bidirectional"))
    )
    (net (code "62") (name "unconnected-(CN1-PadDAT1)") (class "Default")
      (node (ref "CN1") (pin "DAT1") (pinfunction "DAT1_DAT1") (pintype "bidirectional"))
    )
    (net (code "63") (name "unconnected-(CN1-PadDAT2)") (class "Default")
      (node (ref "CN1") (pin "DAT2") (pinfunction "DAT2_DAT2") (pintype "bidirectional"))
    )
    (net (code "64") (name "unconnected-(CN1-PadDET_A)") (class "Default")
      (node (ref "CN1") (pin "DET_A") (pinfunction "DET_A_DET_A") (pintype "bidirectional"))
    )
    (net (code "65") (name "unconnected-(CN1-PadDET_B)") (class "Default")
      (node (ref "CN1") (pin "DET_B") (pinfunction "DET_B_DET_B") (pintype "bidirectional"))
    )
    (net (code "66") (name "unconnected-(IM1-PadIO2)") (class "Default")
      (node (ref "IM1") (pin "IO2") (pinfunction "IO2_IO2") (pintype "bidirectional"))
    )
    (net (code "67") (name "unconnected-(IM1-PadIO3)") (class "Default")
      (node (ref "IM1") (pin "IO3") (pinfunction "IO3_IO3") (pintype "bidirectional"))
    )
    (net (code "68") (name "unconnected-(IM1-PadIO4)") (class "Default")
      (node (ref "IM1") (pin "IO4") (pinfunction "IO4_IO4") (pintype "bidirectional"))
    )
    (net (code "69") (name "unconnected-(IM1-PadIO5)") (class "Default")
      (node (ref "IM1") (pin "IO5") (pinfunction "IO5_IO5") (pintype "bidirectional"))
    )
    (net (code "70") (name "unconnected-(IM1-PadIO8)") (class "Default")
      (node (ref "IM1") (pin "IO8") (pinfunction "IO8_IO8") (pintype "bidirectional"))
    )
    (net (code "71") (name "unconnected-(IM1-PadIO9)") (class "Default")
      (node (ref "IM1") (pin "IO9") (pinfunction "IO9_IO9") (pintype "bidirectional"))
    )
    (net (code "72") (name "unconnected-(IM1-PadIO10)") (class "Default")
      (node (ref "IM1") (pin "IO10") (pinfunction "IO10_IO10") (pintype "bidirectional"))
    )
    (net (code "73") (name "unconnected-(IM1-PadIO11)") (class "Default")
      (node (ref "IM1") (pin "IO11") (pinfunction "IO11_IO11") (pintype "bidirectional"))
    )
    (net (code "74") (name "unconnected-(IM1-PadIO12)") (class "Default")
      (node (ref "IM1") (pin "IO12") (pinfunction "IO12_IO12") (pintype "bidirectional"))
    )
    (net (code "75") (name "unconnected-(IM1-PadIO13)") (class "Default")
      (node (ref "IM1") (pin "IO13") (pinfunction "IO13_IO13") (pintype "bidirectional"))
    )
    (net (code "76") (name "unconnected-(IM1-PadIO14)") (class "Default")
      (node (ref "IM1") (pin "IO14") (pinfunction "IO14_IO14") (pintype "bidirectional"))
    )
    (net (code "77") (name "unconnected-(IM1-PadIO15)") (class "Default")
      (node (ref "IM1") (pin "IO15") (pinfunction "IO15_IO15") (pintype "bidirectional"))
    )
    (net (code "78") (name "unconnected-(IM1-PadIO16)") (class "Default")
      (node (ref "IM1") (pin "IO16") (pinfunction "IO16_IO16") (pintype "bidirectional"))
    )
    (net (code "79") (name "unconnected-(IM1-REG-PadIO22)") (class "Default")
      (node (ref "IM1") (pin "IO22") (pinfunction "REG_IO22") (pintype "bidirectional"))
    )
    (net (code "80") (name "unconnected-(IM1-RESET-PadIO25)") (class "Default")
      (node (ref "IM1") (pin "IO25") (pinfunction "RESET_IO25") (pintype "bidirectional"))
    )
    (net (code "81") (name "unconnected-(IM1-UPDATE-PadIO20)") (class "Default")
      (node (ref "IM1") (pin "IO20") (pinfunction "UPDATE_IO20") (pintype "bidirectional"))
    )
    (net (code "82") (name "unconnected-(JP2-PadP$3)") (class "Default")
      (node (ref "JP2") (pin "P$3") (pinfunction "P$3_P$3") (pintype "bidirectional"))
    )
    (net (code "83") (name "unconnected-(SW1-PadA)") (class "Default")
      (node (ref "SW1") (pin "A") (pinfunction "A_A") (pintype "bidirectional"))
    )
    (net (code "84") (name "unconnected-(SW1-PadC)") (class "Default")
      (node (ref "SW1") (pin "C") (pinfunction "C_C") (pintype "bidirectional"))
    )
    (net (code "85") (name "unconnected-(SW2-PadA)") (class "Default")
      (node (ref "SW2") (pin "A") (pinfunction "A_A") (pintype "bidirectional"))
    )
    (net (code "86") (name "unconnected-(SW2-PadC)") (class "Default")
      (node (ref "SW2") (pin "C") (pinfunction "C_C") (pintype "bidirectional"))
    )
    (net (code "87") (name "unconnected-(SW3-PadR)") (class "Default")
      (node (ref "SW3") (pin "R") (pinfunction "R_R") (pintype "bidirectional"))
    )
    (net (code "88") (name "unconnected-(U$1-1PPS-PadP5)") (class "Default")
      (node (ref "U$1") (pin "P5") (pinfunction "1PPS_P5") (pintype "bidirectional"))
    )
    (net (code "89") (name "unconnected-(U1-CHR0-Pad15)") (class "Default")
      (node (ref "U1") (pin "15") (pinfunction "CHR0_15") (pintype "output"))
    )
    (net (code "90") (name "unconnected-(U1-CHR1-Pad14)") (class "Default")
      (node (ref "U1") (pin "14") (pinfunction "CHR1_14") (pintype "output"))
    )
    (net (code "91") (name "unconnected-(U1-CHREN-Pad13)") (class "Default")
      (node (ref "U1") (pin "13") (pinfunction "CHREN_13") (pintype "output"))
    )
    (net (code "92") (name "unconnected-(U1-GPIO.0{slash}TXT-Pad19)") (class "Default")
      (node (ref "U1") (pin "19") (pinfunction "GPIO.0/TXT_19") (pintype "bidirectional"))
    )
    (net (code "93") (name "unconnected-(U1-GPIO.1{slash}RXT-Pad18)") (class "Default")
      (node (ref "U1") (pin "18") (pinfunction "GPIO.1/RXT_18") (pintype "bidirectional"))
    )
    (net (code "94") (name "unconnected-(U1-GPIO.2{slash}RS485-Pad17)") (class "Default")
      (node (ref "U1") (pin "17") (pinfunction "GPIO.2/RS485_17") (pintype "bidirectional"))
    )
    (net (code "95") (name "unconnected-(U1-GPIO.3{slash}WAKEUP-Pad16)") (class "Default")
      (node (ref "U1") (pin "16") (pinfunction "GPIO.3/WAKEUP_16") (pintype "bidirectional"))
    )
    (net (code "96") (name "unconnected-(U1-GPIO.4-Pad22)") (class "Default")
      (node (ref "U1") (pin "22") (pinfunction "GPIO.4_22") (pintype "bidirectional"))
    )
    (net (code "97") (name "unconnected-(U1-GPIO.5-Pad21)") (class "Default")
      (node (ref "U1") (pin "21") (pinfunction "GPIO.5_21") (pintype "bidirectional"))
    )
    (net (code "98") (name "unconnected-(U1-GPIO.6-Pad20)") (class "Default")
      (node (ref "U1") (pin "20") (pinfunction "GPIO.6_20") (pintype "bidirectional"))
    )
    (net (code "99") (name "unconnected-(U1-NC-Pad10)") (class "Default")
      (node (ref "U1") (pin "10") (pinfunction "NC_10") (pintype "no_connect"))
    )
    (net (code "100") (name "unconnected-(U1-SUSPEND-Pad12)") (class "Default")
      (node (ref "U1") (pin "12") (pinfunction "SUSPEND_12") (pintype "output"))
    )
    (net (code "101") (name "unconnected-(USB1-4_ID-Pad4)") (class "Default")
      (node (ref "USB1") (pin "4") (pinfunction "4_ID_4") (pintype "bidirectional"))
    )
  )
)
